# 2012_fdp_balise_mere.net
KiCad netlist of a schematic drawn in Altium Designer
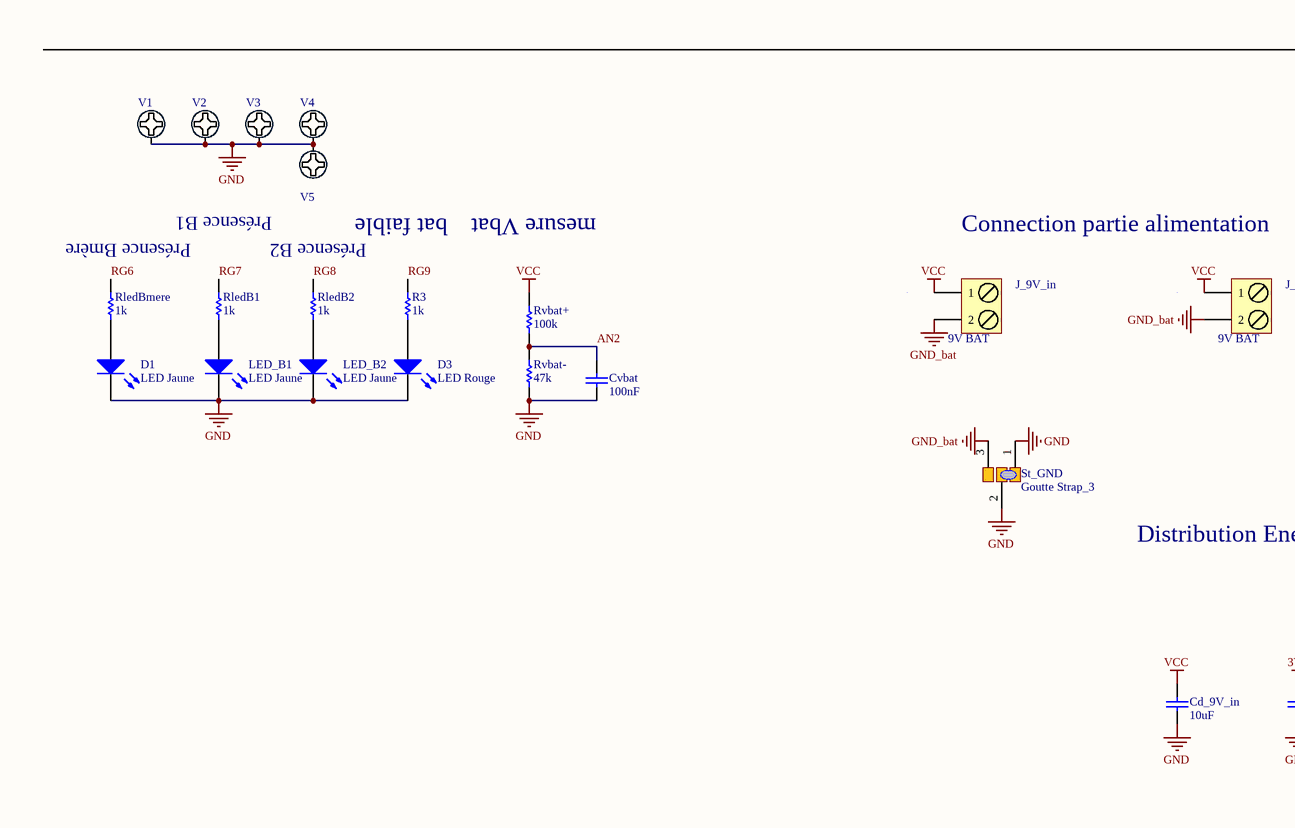
[diagram p0: 2012_fdp_balise_mere.SchDoc, left]
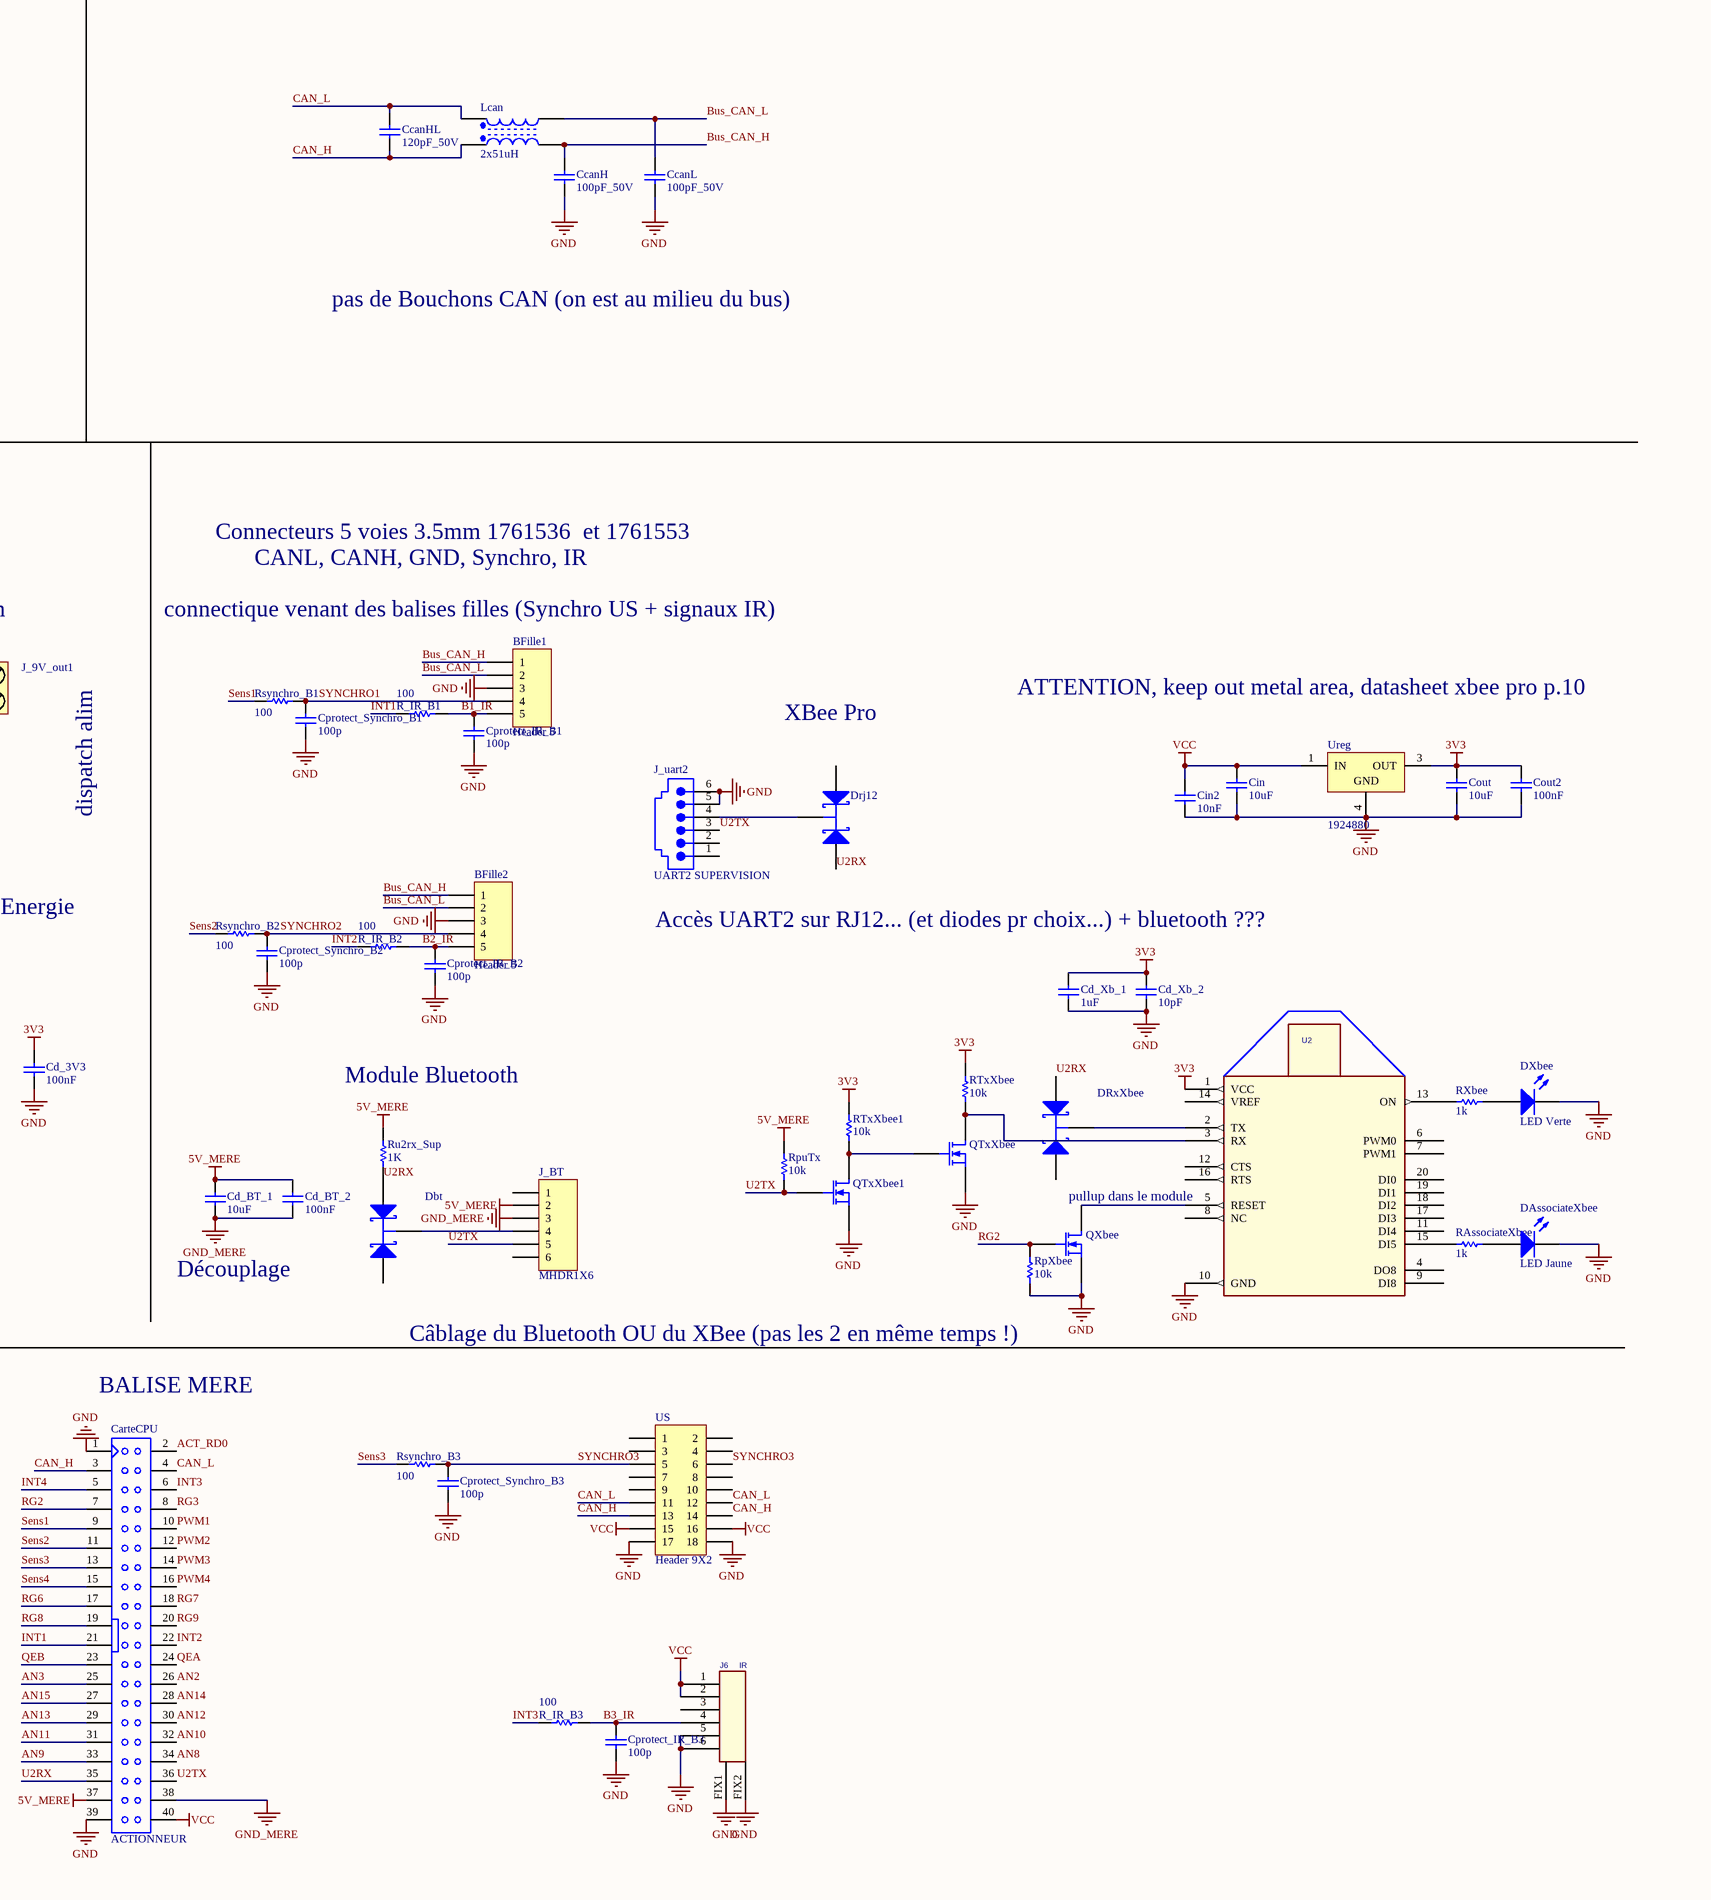
[diagram p1: 2012_fdp_balise_mere.SchDoc, right]

(export (version "E")
  (design (tool "Eeschema 10.0.6"))
  (components
    (comp (ref "BFille1")
      (value "Header 5")
      (footprint "BORNIER_5V_3.5MM")
      (description "Header, 5-Pin")
      (fields (field (name "PUBLISHER") "Altium Limited"))
      (libsource (lib "DG_Connecteur") (part "Header 5"))
    )
    (comp (ref "BFille2")
      (value "Header 5")
      (footprint "BORNIER_5V_3.5MM")
      (description "Header, 5-Pin")
      (fields (field (name "PUBLISHER") "Altium Limited"))
      (libsource (lib "DG_Connecteur") (part "Header 5"))
    )
    (comp (ref "CarteCPU")
      (value "ACTIONNEUR")
      (footprint "HE10/40_MAL_DROIT-FDP-ROBOT")
      (description "Connector; HE10; 40 Position; Male")
      (libsource (lib "miniprojet") (part "HE10/40"))
    )
    (comp (ref "CcanH")
      (value "100pF_50V")
      (footprint "C0603_N")
      (description "Capacitor")
      (fields (field (name "PUBLISHER") "Altium Limited"))
      (libsource (lib "DG_Condensateur") (part "Capacitor"))
    )
    (comp (ref "CcanHL")
      (value "120pF_50V")
      (footprint "C0603_N")
      (description "Capacitor")
      (fields (field (name "PUBLISHER") "Altium Limited"))
      (libsource (lib "DG_Condensateur") (part "Capacitor"))
    )
    (comp (ref "CcanL")
      (value "100pF_50V")
      (footprint "C0603_N")
      (description "Capacitor")
      (fields (field (name "PUBLISHER") "Altium Limited"))
      (libsource (lib "DG_Condensateur") (part "Capacitor"))
    )
    (comp (ref "Cd_3V3")
      (value "100nF")
      (footprint "C0805_N")
      (description "Capacitor")
      (fields (field (name "PUBLISHER") "Altium Limited"))
      (libsource (lib "_ROBOT") (part "Condensateur"))
    )
    (comp (ref "Cd_9V_in")
      (value "10uF")
      (footprint "C0805_N")
      (description "Capacitor")
      (fields (field (name "PUBLISHER") "Altium Limited"))
      (libsource (lib "_ROBOT") (part "Condensateur"))
    )
    (comp (ref "Cd_BT_1")
      (value "10uF")
      (footprint "C0805_N")
      (description "Capacitor")
      (fields (field (name "PUBLISHER") "Altium Limited"))
      (libsource (lib "_ROBOT") (part "Condensateur"))
    )
    (comp (ref "Cd_BT_2")
      (value "100nF")
      (footprint "C0805_N")
      (description "Capacitor")
      (fields (field (name "PUBLISHER") "Altium Limited"))
      (libsource (lib "_ROBOT") (part "Condensateur"))
    )
    (comp (ref "Cd_Xb_1")
      (value "1uF")
      (footprint "C0805_N")
      (description "Capacitor")
      (fields (field (name "PUBLISHER") "Altium Limited"))
      (libsource (lib "_ROBOT") (part "Condensateur"))
    )
    (comp (ref "Cd_Xb_2")
      (value "10pF")
      (footprint "C0805_N")
      (description "Capacitor")
      (fields (field (name "PUBLISHER") "Altium Limited"))
      (libsource (lib "_ROBOT") (part "Condensateur"))
    )
    (comp (ref "Cin")
      (value "10uF")
      (footprint "C1206_N")
      (description "Capacitor")
      (fields (field (name "PUBLISHER") "Altium Limited"))
      (libsource (lib "DG_Condensateur") (part "Capacitor"))
    )
    (comp (ref "Cin2")
      (value "10nF")
      (footprint "C0805_N")
      (description "Capacitor")
      (fields (field (name "PUBLISHER") "Altium Limited"))
      (libsource (lib "DG_Condensateur") (part "Capacitor"))
    )
    (comp (ref "Cout")
      (value "10uF")
      (footprint "C1206_N")
      (description "Capacitor")
      (fields (field (name "PUBLISHER") "Altium Limited"))
      (libsource (lib "DG_Condensateur") (part "Capacitor"))
    )
    (comp (ref "Cout2")
      (value "100nF")
      (footprint "C0805_N")
      (description "Capacitor")
      (fields (field (name "PUBLISHER") "Altium Limited"))
      (libsource (lib "DG_Condensateur") (part "Capacitor"))
    )
    (comp (ref "Cprotect_IR_B1")
      (value "100p")
      (footprint "C0805_N")
      (description "Capacitor")
      (fields (field (name "PUBLISHER") "Altium Limited"))
      (libsource (lib "DG_Condensateur") (part "Capacitor"))
    )
    (comp (ref "Cprotect_IR_B2")
      (value "100p")
      (footprint "C0805_N")
      (description "Capacitor")
      (fields (field (name "PUBLISHER") "Altium Limited"))
      (libsource (lib "DG_Condensateur") (part "Capacitor"))
    )
    (comp (ref "Cprotect_IR_B3")
      (value "100p")
      (footprint "C0805_N")
      (description "Capacitor")
      (fields (field (name "PUBLISHER") "Altium Limited"))
      (libsource (lib "DG_Condensateur") (part "Capacitor"))
    )
    (comp (ref "Cprotect_Synchro_B1")
      (value "100p")
      (footprint "C0805_N")
      (description "Capacitor")
      (fields (field (name "PUBLISHER") "Altium Limited"))
      (libsource (lib "DG_Condensateur") (part "Capacitor"))
    )
    (comp (ref "Cprotect_Synchro_B2")
      (value "100p")
      (footprint "C0805_N")
      (description "Capacitor")
      (fields (field (name "PUBLISHER") "Altium Limited"))
      (libsource (lib "DG_Condensateur") (part "Capacitor"))
    )
    (comp (ref "Cprotect_Synchro_B3")
      (value "100p")
      (footprint "C0805_N")
      (description "Capacitor")
      (fields (field (name "PUBLISHER") "Altium Limited"))
      (libsource (lib "DG_Condensateur") (part "Capacitor"))
    )
    (comp (ref "Cvbat")
      (value "100nF")
      (footprint "C0805_N")
      (description "Capacitor")
      (fields (field (name "PUBLISHER") "Altium Limited"))
      (libsource (lib "DG_Condensateur") (part "Capacitor"))
    )
    (comp (ref "D1")
      (value "LED Jaune")
      (footprint "LED_0805")
      (description "Typical LED")
      (fields (field (name "PUBLISHER") "Altium Limited"))
      (libsource (lib "_ROBOT") (part "LED"))
    )
    (comp (ref "D3")
      (value "LED Rouge")
      (footprint "LED_0805")
      (description "Typical LED")
      (fields (field (name "PUBLISHER") "Altium Limited"))
      (libsource (lib "_ROBOT") (part "LED"))
    )
    (comp (ref "DAssociateXbee")
      (value "LED Jaune")
      (footprint "LED_0805")
      (description "Typical LED")
      (fields (field (name "PUBLISHER") "Altium Limited"))
      (libsource (lib "_ROBOT") (part "LED"))
    )
    (comp (ref "Dbt")
      (value "Diode Shottky double BAT54C")
      (footprint "SOT23-3N")
      (description "DIODE SCHOTTKY DOUBLE")
      (fields (field (name "MANUFACTURER PART NUMBER") "BAT54C") (field (name "MANUFACTURER") "ZETEX"))
      (libsource (lib "_ROBOT") (part "Diode Shottky double BAT54C"))
    )
    (comp (ref "Drj12")
      (value "Diode Shottky double BAT54C")
      (footprint "SOT23-3N")
      (description "DIODE SCHOTTKY DOUBLE")
      (fields (field (name "MANUFACTURER PART NUMBER") "BAT54C") (field (name "MANUFACTURER") "ZETEX"))
      (libsource (lib "_ROBOT") (part "Diode Shottky double BAT54C"))
    )
    (comp (ref "DRxXbee")
      (value "Diode Shottky double BAT54C")
      (footprint "SOT23-3N")
      (description "DIODE SCHOTTKY DOUBLE")
      (fields (field (name "MANUFACTURER PART NUMBER") "BAT54C") (field (name "MANUFACTURER") "ZETEX"))
      (libsource (lib "_ROBOT") (part "Diode Shottky double BAT54C"))
    )
    (comp (ref "DXbee")
      (value "LED Verte")
      (footprint "LED_0805")
      (description "Typical LED")
      (fields (field (name "PUBLISHER") "Altium Limited"))
      (libsource (lib "_ROBOT") (part "LED"))
    )
    (comp (ref "J6")
      (value "IR")
      (footprint "RJ11_6/6 - droit")
      (libsource (lib "*") (part "CONNECTEUR_RJ12"))
    )
    (comp (ref "J_9V_in")
      (value "9V BAT")
      (footprint "BORNIER2")
      (description "Terminal blocks, 2 pins, pitch=5mm")
      (libsource (lib "miniprojet") (part "BORNIER2"))
    )
    (comp (ref "J_9V_out1")
      (value "9V BAT")
      (footprint "BORNIER2")
      (description "Terminal blocks, 2 pins, pitch=5mm")
      (libsource (lib "miniprojet") (part "BORNIER2"))
    )
    (comp (ref "J_BT")
      (value "MHDR1X6")
      (footprint "HE14_6")
      (description "Header, 6-Pin")
      (fields (field (name "PUBLISHER") "Altium Limited"))
      (libsource (lib "Miscellaneous Connectors") (part "MHDR1X6"))
    )
    (comp (ref "J_uart2")
      (value "UART2 SUPERVISION")
      (footprint "RJ11_6/6")
      (description "Right Angle, Standard Profile, Offset Latch DECconnect, Flangeless PCB Jack")
      (fields (field (name "PUBLISHER") "Altium Limited"))
      (libsource (lib "miniprojet") (part "RJ11_6/6"))
    )
    (comp (ref "Lcan")
      (value "2x51uH")
      (footprint "Self de mode commun Wurth Elektronik WE-SL2")
      (description "WUERTH ELEKTRONIK - WE-SL2 744 227 - FILTRE DE LIGNE MODE COMMUN CMS 2X51uH")
      (fields (field (name "MANUFACTURER") "WURTH ELEKTRONIK"))
      (libsource (lib "DG_Inductance") (part "Self de mode commun WE-744220"))
    )
    (comp (ref "LED_B1")
      (value "LED Jaune")
      (footprint "LED_0805")
      (description "Typical LED")
      (fields (field (name "PUBLISHER") "Altium Limited"))
      (libsource (lib "_ROBOT") (part "LED"))
    )
    (comp (ref "LED_B2")
      (value "LED Jaune")
      (footprint "LED_0805")
      (description "Typical LED")
      (fields (field (name "PUBLISHER") "Altium Limited"))
      (libsource (lib "_ROBOT") (part "LED"))
    )
    (comp (ref "QTxXbee")
      (value "Transistor MOSFET-N")
      (footprint "SOT23-3N")
      (description "N-Channel MOSFET")
      (fields (field (name "PUBLISHER") "Altium Limited"))
      (libsource (lib "_ROBOT") (part "Transistor MOSFET-N"))
    )
    (comp (ref "QTxXbee1")
      (value "Transistor MOSFET-N")
      (footprint "SOT23-3N")
      (description "N-Channel MOSFET")
      (fields (field (name "PUBLISHER") "Altium Limited"))
      (libsource (lib "_ROBOT") (part "Transistor MOSFET-N"))
    )
    (comp (ref "QXbee")
      (value "Transistor MOSFET-N")
      (footprint "SOT23-3N")
      (description "N-Channel MOSFET")
      (fields (field (name "PUBLISHER") "Altium Limited"))
      (libsource (lib "_ROBOT") (part "Transistor MOSFET-N"))
    )
    (comp (ref "R3")
      (value "1k")
      (footprint "R1206_N")
      (description "Resistor")
      (fields (field (name "PUBLISHER") "Altium Limited"))
      (libsource (lib "_ROBOT") (part "Resistor"))
    )
    (comp (ref "RAssociateXbee")
      (value "1k")
      (footprint "R1206_N")
      (description "Resistor")
      (fields (field (name "PUBLISHER") "Altium Limited"))
      (libsource (lib "_ROBOT") (part "Resistor"))
    )
    (comp (ref "RledB1")
      (value "1k")
      (footprint "R1206_N")
      (description "Resistor")
      (fields (field (name "PUBLISHER") "Altium Limited"))
      (libsource (lib "_ROBOT") (part "Resistor"))
    )
    (comp (ref "RledB2")
      (value "1k")
      (footprint "R1206_N")
      (description "Resistor")
      (fields (field (name "PUBLISHER") "Altium Limited"))
      (libsource (lib "_ROBOT") (part "Resistor"))
    )
    (comp (ref "RledBmere")
      (value "1k")
      (footprint "R1206_N")
      (description "Resistor")
      (fields (field (name "PUBLISHER") "Altium Limited"))
      (libsource (lib "_ROBOT") (part "Resistor"))
    )
    (comp (ref "RpuTx")
      (value "10k")
      (footprint "R1206_N")
      (description "Resistor")
      (fields (field (name "PUBLISHER") "Altium Limited"))
      (libsource (lib "_ROBOT") (part "Resistor"))
    )
    (comp (ref "RpXbee")
      (value "10k")
      (footprint "R1206_N")
      (description "Resistor")
      (fields (field (name "PUBLISHER") "Altium Limited"))
      (libsource (lib "_ROBOT") (part "Resistor"))
    )
    (comp (ref "Rsynchro_B1")
      (value "100")
      (footprint "R1206_N")
      (description "Resistor")
      (fields (field (name "PUBLISHER") "Altium Limited"))
      (libsource (lib "_ROBOT") (part "Resistor"))
    )
    (comp (ref "Rsynchro_B2")
      (value "100")
      (footprint "R1206_N")
      (description "Resistor")
      (fields (field (name "PUBLISHER") "Altium Limited"))
      (libsource (lib "_ROBOT") (part "Resistor"))
    )
    (comp (ref "Rsynchro_B3")
      (value "100")
      (footprint "R1206_N")
      (description "Resistor")
      (fields (field (name "PUBLISHER") "Altium Limited"))
      (libsource (lib "_ROBOT") (part "Resistor"))
    )
    (comp (ref "RTxXbee")
      (value "10k")
      (footprint "R1206_N")
      (description "Resistor")
      (fields (field (name "PUBLISHER") "Altium Limited"))
      (libsource (lib "_ROBOT") (part "Resistor"))
    )
    (comp (ref "RTxXbee1")
      (value "10k")
      (footprint "R1206_N")
      (description "Resistor")
      (fields (field (name "PUBLISHER") "Altium Limited"))
      (libsource (lib "_ROBOT") (part "Resistor"))
    )
    (comp (ref "Ru2rx_Sup")
      (value "1K")
      (footprint "R1206_N")
      (description "Resistor")
      (fields (field (name "PUBLISHER") "Altium Limited"))
      (libsource (lib "_ROBOT") (part "Resistor"))
    )
    (comp (ref "Rvbat+")
      (value "100k")
      (footprint "R1206_N")
      (description "Resistor")
      (fields (field (name "PUBLISHER") "Altium Limited"))
      (libsource (lib "_ROBOT") (part "Resistor"))
    )
    (comp (ref "Rvbat-")
      (value "47k")
      (footprint "R1206_N")
      (description "Resistor")
      (fields (field (name "PUBLISHER") "Altium Limited"))
      (libsource (lib "_ROBOT") (part "Resistor"))
    )
    (comp (ref "RXbee")
      (value "1k")
      (footprint "R1206_N")
      (description "Resistor")
      (fields (field (name "PUBLISHER") "Altium Limited"))
      (libsource (lib "_ROBOT") (part "Resistor"))
    )
    (comp (ref "R_IR_B1")
      (value "100")
      (footprint "R1206_N")
      (description "Resistor")
      (fields (field (name "PUBLISHER") "Altium Limited"))
      (libsource (lib "_ROBOT") (part "Resistor"))
    )
    (comp (ref "R_IR_B2")
      (value "100")
      (footprint "R1206_N")
      (description "Resistor")
      (fields (field (name "PUBLISHER") "Altium Limited"))
      (libsource (lib "_ROBOT") (part "Resistor"))
    )
    (comp (ref "R_IR_B3")
      (value "100")
      (footprint "R1206_N")
      (description "Resistor")
      (fields (field (name "PUBLISHER") "Altium Limited"))
      (libsource (lib "_ROBOT") (part "Resistor"))
    )
    (comp (ref "St_GND")
      (value "Goutte Strap_3")
      (footprint "Goutte Strap_3")
      (fields (field (name "PUBLISHER") "Damien Guitton"))
      (libsource (lib "DG_Connecteur") (part "Goutte Strap_3"))
    )
    (comp (ref "U2") (value "XBee") (footprint "MODULE_XBEE") (libsource (lib "*") (part "XBee")))
    (comp (ref "Ureg")
      (value "1924880")
      (footprint "369A-13")
      (description "Three-Terminal Positive Voltage Regulator")
      (fields (field (name "PUBLISHER") "Altium Limited"))
      (libsource (lib "ON Semi Power Mgt Voltage Regulator") (part "MC7805ACD2T"))
    )
    (comp (ref "US")
      (value "Header 9X2")
      (footprint "HDR2X9")
      (description "Header, 9-Pin, Dual row")
      (fields (field (name "PUBLISHER") "Altium Limited"))
      (libsource (lib "DG_Connecteur") (part "Header 9X2"))
    )
    (comp (ref "V1")
      (value "Pad_M3")
      (footprint "M3x6mm")
      (description "Vis M3 X 6mm _TORX_Tête 6mm")
      (fields (field (name "PUBLISHER") "Damien Guitton"))
      (libsource (lib "_ROBOT") (part "Vis M3 X 6mm _TORX_Tête 6mm"))
    )
    (comp (ref "V2")
      (value "Pad_M3")
      (footprint "M3x6mm")
      (description "Vis M3 X 6mm _TORX_Tête 6mm")
      (fields (field (name "PUBLISHER") "Damien Guitton"))
      (libsource (lib "_ROBOT") (part "Vis M3 X 6mm _TORX_Tête 6mm"))
    )
    (comp (ref "V3")
      (value "Pad_M3")
      (footprint "M3x6mm")
      (description "Vis M3 X 6mm _TORX_Tête 6mm")
      (fields (field (name "PUBLISHER") "Damien Guitton"))
      (libsource (lib "_ROBOT") (part "Vis M3 X 6mm _TORX_Tête 6mm"))
    )
    (comp (ref "V4")
      (value "Pad_M3")
      (footprint "M3x6mm")
      (description "Vis M3 X 6mm _TORX_Tête 6mm")
      (fields (field (name "PUBLISHER") "Damien Guitton"))
      (libsource (lib "_ROBOT") (part "Vis M3 X 6mm _TORX_Tête 6mm"))
    )
    (comp (ref "V5")
      (value "Pad_M3")
      (footprint "M3x6mm")
      (description "Vis M3 X 6mm _TORX_Tête 6mm")
      (fields (field (name "PUBLISHER") "Damien Guitton"))
      (libsource (lib "_ROBOT") (part "Vis M3 X 6mm _TORX_Tête 6mm"))
    )
  )
  (nets
    (net (code "1") (name "/ACT_RD0") (class "Default")
      (node (ref "CarteCPU") (pin "2") (pinfunction "2_2") (pintype "passive"))
    )
    (net (code "2") (name "/AN2") (class "Default")
      (node (ref "CarteCPU") (pin "26") (pinfunction "26_26") (pintype "passive"))
      (node (ref "Cvbat") (pin "1") (pinfunction "1_1") (pintype "passive"))
      (node (ref "Rvbat+") (pin "2") (pinfunction "2_2") (pintype "passive"))
      (node (ref "Rvbat-") (pin "1") (pinfunction "1_1") (pintype "passive"))
    )
    (net (code "3") (name "/AN3") (class "Default")
      (node (ref "CarteCPU") (pin "25") (pinfunction "25_25") (pintype "passive"))
    )
    (net (code "4") (name "/AN8") (class "Default")
      (node (ref "CarteCPU") (pin "34") (pinfunction "34_34") (pintype "passive"))
    )
    (net (code "5") (name "/AN9") (class "Default")
      (node (ref "CarteCPU") (pin "33") (pinfunction "33_33") (pintype "passive"))
    )
    (net (code "6") (name "/AN10") (class "Default")
      (node (ref "CarteCPU") (pin "32") (pinfunction "32_32") (pintype "passive"))
    )
    (net (code "7") (name "/AN11") (class "Default")
      (node (ref "CarteCPU") (pin "31") (pinfunction "31_31") (pintype "passive"))
    )
    (net (code "8") (name "/AN12") (class "Default")
      (node (ref "CarteCPU") (pin "30") (pinfunction "30_30") (pintype "passive"))
    )
    (net (code "9") (name "/AN13") (class "Default")
      (node (ref "CarteCPU") (pin "29") (pinfunction "29_29") (pintype "passive"))
    )
    (net (code "10") (name "/AN14") (class "Default")
      (node (ref "CarteCPU") (pin "28") (pinfunction "28_28") (pintype "passive"))
    )
    (net (code "11") (name "/AN15") (class "Default")
      (node (ref "CarteCPU") (pin "27") (pinfunction "27_27") (pintype "passive"))
    )
    (net (code "12") (name "/B1_IR") (class "Default")
      (node (ref "BFille1") (pin "5") (pinfunction "5_5") (pintype "passive"))
      (node (ref "Cprotect_IR_B1") (pin "1") (pinfunction "1_1") (pintype "passive"))
      (node (ref "R_IR_B1") (pin "2") (pinfunction "2_2") (pintype "passive"))
    )
    (net (code "13") (name "/B2_IR") (class "Default")
      (node (ref "BFille2") (pin "5") (pinfunction "5_5") (pintype "passive"))
      (node (ref "Cprotect_IR_B2") (pin "1") (pinfunction "1_1") (pintype "passive"))
      (node (ref "R_IR_B2") (pin "2") (pinfunction "2_2") (pintype "passive"))
    )
    (net (code "14") (name "/B3_IR") (class "Default")
      (node (ref "Cprotect_IR_B3") (pin "1") (pinfunction "1_1") (pintype "passive"))
      (node (ref "J6") (pin "4") (pinfunction "4_4") (pintype "passive"))
      (node (ref "R_IR_B3") (pin "2") (pinfunction "2_2") (pintype "passive"))
    )
    (net (code "15") (name "/Bus_CAN_H") (class "Default")
      (node (ref "BFille1") (pin "1") (pinfunction "1_1") (pintype "passive"))
      (node (ref "BFille2") (pin "1") (pinfunction "1_1") (pintype "passive"))
      (node (ref "CcanH") (pin "2") (pinfunction "2_2") (pintype "passive"))
      (node (ref "Lcan") (pin "4") (pinfunction "4_4") (pintype "passive"))
    )
    (net (code "16") (name "/Bus_CAN_L") (class "Default")
      (node (ref "BFille1") (pin "2") (pinfunction "2_2") (pintype "passive"))
      (node (ref "BFille2") (pin "2") (pinfunction "2_2") (pintype "passive"))
      (node (ref "CcanL") (pin "2") (pinfunction "2_2") (pintype "passive"))
      (node (ref "Lcan") (pin "3") (pinfunction "3_3") (pintype "passive"))
    )
    (net (code "17") (name "/CAN_H") (class "Default")
      (node (ref "CarteCPU") (pin "3") (pinfunction "3_3") (pintype "passive"))
      (node (ref "CcanHL") (pin "1") (pinfunction "1_1") (pintype "passive"))
      (node (ref "Lcan") (pin "1") (pinfunction "1_1") (pintype "passive"))
      (node (ref "US") (pin "13") (pinfunction "13_13") (pintype "passive"))
      (node (ref "US") (pin "14") (pinfunction "14_14") (pintype "passive"))
    )
    (net (code "18") (name "/CAN_L") (class "Default")
      (node (ref "CarteCPU") (pin "4") (pinfunction "4_4") (pintype "passive"))
      (node (ref "CcanHL") (pin "2") (pinfunction "2_2") (pintype "passive"))
      (node (ref "Lcan") (pin "2") (pinfunction "2_2") (pintype "passive"))
      (node (ref "US") (pin "11") (pinfunction "11_11") (pintype "passive"))
      (node (ref "US") (pin "12") (pinfunction "12_12") (pintype "passive"))
    )
    (net (code "19") (name "/INT1") (class "Default")
      (node (ref "CarteCPU") (pin "21") (pinfunction "21_21") (pintype "passive"))
      (node (ref "R_IR_B1") (pin "1") (pinfunction "1_1") (pintype "passive"))
    )
    (net (code "20") (name "/INT2") (class "Default")
      (node (ref "CarteCPU") (pin "22") (pinfunction "22_22") (pintype "passive"))
      (node (ref "R_IR_B2") (pin "1") (pinfunction "1_1") (pintype "passive"))
    )
    (net (code "21") (name "/INT3") (class "Default")
      (node (ref "CarteCPU") (pin "6") (pinfunction "6_6") (pintype "passive"))
      (node (ref "R_IR_B3") (pin "1") (pinfunction "1_1") (pintype "passive"))
    )
    (net (code "22") (name "/INT4") (class "Default")
      (node (ref "CarteCPU") (pin "5") (pinfunction "5_5") (pintype "passive"))
    )
    (net (code "23") (name "/PWM1") (class "Default")
      (node (ref "CarteCPU") (pin "10") (pinfunction "10_10") (pintype "passive"))
    )
    (net (code "24") (name "/PWM2") (class "Default")
      (node (ref "CarteCPU") (pin "12") (pinfunction "12_12") (pintype "passive"))
    )
    (net (code "25") (name "/PWM3") (class "Default")
      (node (ref "CarteCPU") (pin "14") (pinfunction "14_14") (pintype "passive"))
    )
    (net (code "26") (name "/PWM4") (class "Default")
      (node (ref "CarteCPU") (pin "16") (pinfunction "16_16") (pintype "passive"))
    )
    (net (code "27") (name "/QEA") (class "Default")
      (node (ref "CarteCPU") (pin "24") (pinfunction "24_24") (pintype "passive"))
    )
    (net (code "28") (name "/QEB") (class "Default")
      (node (ref "CarteCPU") (pin "23") (pinfunction "23_23") (pintype "passive"))
    )
    (net (code "29") (name "/RG2") (class "Default")
      (node (ref "CarteCPU") (pin "7") (pinfunction "7_7") (pintype "passive"))
      (node (ref "QXbee") (pin "2") (pinfunction "G_2") (pintype "passive"))
      (node (ref "RpXbee") (pin "1") (pinfunction "1_1") (pintype "passive"))
    )
    (net (code "30") (name "/RG3") (class "Default")
      (node (ref "CarteCPU") (pin "8") (pinfunction "8_8") (pintype "passive"))
    )
    (net (code "31") (name "/RG6") (class "Default")
      (node (ref "CarteCPU") (pin "17") (pinfunction "17_17") (pintype "passive"))
      (node (ref "RledBmere") (pin "1") (pinfunction "1_1") (pintype "passive"))
    )
    (net (code "32") (name "/RG7") (class "Default")
      (node (ref "CarteCPU") (pin "18") (pinfunction "18_18") (pintype "passive"))
      (node (ref "RledB1") (pin "2") (pinfunction "2_2") (pintype "passive"))
    )
    (net (code "33") (name "/RG8") (class "Default")
      (node (ref "CarteCPU") (pin "19") (pinfunction "19_19") (pintype "passive"))
      (node (ref "RledB2") (pin "2") (pinfunction "2_2") (pintype "passive"))
    )
    (net (code "34") (name "/RG9") (class "Default")
      (node (ref "CarteCPU") (pin "20") (pinfunction "20_20") (pintype "passive"))
      (node (ref "R3") (pin "1") (pinfunction "1_1") (pintype "passive"))
    )
    (net (code "35") (name "/SYNCHRO1") (class "Default")
      (node (ref "BFille1") (pin "4") (pinfunction "4_4") (pintype "passive"))
      (node (ref "Cprotect_Synchro_B1") (pin "1") (pinfunction "1_1") (pintype "passive"))
      (node (ref "Rsynchro_B1") (pin "2") (pinfunction "2_2") (pintype "passive"))
    )
    (net (code "36") (name "/SYNCHRO2") (class "Default")
      (node (ref "BFille2") (pin "4") (pinfunction "4_4") (pintype "passive"))
      (node (ref "Cprotect_Synchro_B2") (pin "1") (pinfunction "1_1") (pintype "passive"))
      (node (ref "Rsynchro_B2") (pin "2") (pinfunction "2_2") (pintype "passive"))
    )
    (net (code "37") (name "/SYNCHRO3") (class "Default")
      (node (ref "Cprotect_Synchro_B3") (pin "1") (pinfunction "1_1") (pintype "passive"))
      (node (ref "Rsynchro_B3") (pin "2") (pinfunction "2_2") (pintype "passive"))
      (node (ref "US") (pin "5") (pinfunction "5_5") (pintype "passive"))
      (node (ref "US") (pin "6") (pinfunction "6_6") (pintype "passive"))
    )
    (net (code "38") (name "/Sens1") (class "Default")
      (node (ref "CarteCPU") (pin "9") (pinfunction "9_9") (pintype "passive"))
      (node (ref "Rsynchro_B1") (pin "1") (pinfunction "1_1") (pintype "passive"))
    )
    (net (code "39") (name "/Sens2") (class "Default")
      (node (ref "CarteCPU") (pin "11") (pinfunction "11_11") (pintype "passive"))
      (node (ref "Rsynchro_B2") (pin "1") (pinfunction "1_1") (pintype "passive"))
    )
    (net (code "40") (name "/Sens3") (class "Default")
      (node (ref "CarteCPU") (pin "13") (pinfunction "13_13") (pintype "passive"))
      (node (ref "Rsynchro_B3") (pin "1") (pinfunction "1_1") (pintype "passive"))
    )
    (net (code "41") (name "/Sens4") (class "Default")
      (node (ref "CarteCPU") (pin "15") (pinfunction "15_15") (pintype "passive"))
    )
    (net (code "42") (name "/U2RX") (class "Default")
      (node (ref "CarteCPU") (pin "35") (pinfunction "35_35") (pintype "passive"))
      (node (ref "DRxXbee") (pin "1") (pinfunction "A1_1") (pintype "passive"))
      (node (ref "Dbt") (pin "1") (pinfunction "A1_1") (pintype "passive"))
      (node (ref "Drj12") (pin "1") (pinfunction "A1_1") (pintype "passive"))
      (node (ref "Ru2rx_Sup") (pin "1") (pinfunction "1_1") (pintype "passive"))
    )
    (net (code "43") (name "/U2TX") (class "Default")
      (node (ref "CarteCPU") (pin "36") (pinfunction "36_36") (pintype "passive"))
      (node (ref "J_BT") (pin "5") (pinfunction "5_5") (pintype "passive"))
      (node (ref "J_uart2") (pin "3") (pinfunction "3_3") (pintype "passive"))
      (node (ref "QTxXbee1") (pin "2") (pinfunction "G_2") (pintype "passive"))
      (node (ref "RpuTx") (pin "2") (pinfunction "2_2") (pintype "passive"))
    )
    (net (code "44") (name "3V3") (class "Default")
      (node (ref "Cd_3V3") (pin "2") (pinfunction "2_2") (pintype "passive"))
      (node (ref "Cd_Xb_1") (pin "2") (pinfunction "2_2") (pintype "passive"))
      (node (ref "Cd_Xb_2") (pin "2") (pinfunction "2_2") (pintype "passive"))
      (node (ref "Cout") (pin "2") (pinfunction "2_2") (pintype "passive"))
      (node (ref "Cout2") (pin "2") (pinfunction "2_2") (pintype "passive"))
      (node (ref "RTxXbee") (pin "1") (pinfunction "1_1") (pintype "passive"))
      (node (ref "RTxXbee1") (pin "1") (pinfunction "1_1") (pintype "passive"))
      (node (ref "U2") (pin "1") (pinfunction "VCC_1") (pintype "output"))
      (node (ref "Ureg") (pin "3") (pinfunction "OUT_3") (pintype "power_in"))
    )
    (net (code "45") (name "5V_MERE") (class "Default")
      (node (ref "CarteCPU") (pin "37") (pinfunction "37_37") (pintype "passive"))
      (node (ref "Cd_BT_1") (pin "2") (pinfunction "2_2") (pintype "passive"))
      (node (ref "Cd_BT_2") (pin "2") (pinfunction "2_2") (pintype "passive"))
      (node (ref "J_BT") (pin "2") (pinfunction "2_2") (pintype "passive"))
      (node (ref "RpuTx") (pin "1") (pinfunction "1_1") (pintype "passive"))
      (node (ref "Ru2rx_Sup") (pin "2") (pinfunction "2_2") (pintype "passive"))
    )
    (net (code "46") (name "GND") (class "Default")
      (node (ref "BFille1") (pin "3") (pinfunction "3_3") (pintype "passive"))
      (node (ref "BFille2") (pin "3") (pinfunction "3_3") (pintype "passive"))
      (node (ref "CarteCPU") (pin "1") (pinfunction "1_1") (pintype "passive"))
      (node (ref "CarteCPU") (pin "39") (pinfunction "39_39") (pintype "passive"))
      (node (ref "CcanH") (pin "1") (pinfunction "1_1") (pintype "passive"))
      (node (ref "CcanL") (pin "1") (pinfunction "1_1") (pintype "passive"))
      (node (ref "Cd_3V3") (pin "1") (pinfunction "1_1") (pintype "passive"))
      (node (ref "Cd_9V_in") (pin "1") (pinfunction "1_1") (pintype "passive"))
      (node (ref "Cd_Xb_1") (pin "1") (pinfunction "1_1") (pintype "passive"))
      (node (ref "Cd_Xb_2") (pin "1") (pinfunction "1_1") (pintype "passive"))
      (node (ref "Cin") (pin "1") (pinfunction "1_1") (pintype "passive"))
      (node (ref "Cin2") (pin "1") (pinfunction "1_1") (pintype "passive"))
      (node (ref "Cout") (pin "1") (pinfunction "1_1") (pintype "passive"))
      (node (ref "Cout2") (pin "1") (pinfunction "1_1") (pintype "passive"))
      (node (ref "Cprotect_IR_B1") (pin "2") (pinfunction "2_2") (pintype "passive"))
      (node (ref "Cprotect_IR_B2") (pin "2") (pinfunction "2_2") (pintype "passive"))
      (node (ref "Cprotect_IR_B3") (pin "2") (pinfunction "2_2") (pintype "passive"))
      (node (ref "Cprotect_Synchro_B1") (pin "2") (pinfunction "2_2") (pintype "passive"))
      (node (ref "Cprotect_Synchro_B2") (pin "2") (pinfunction "2_2") (pintype "passive"))
      (node (ref "Cprotect_Synchro_B3") (pin "2") (pinfunction "2_2") (pintype "passive"))
      (node (ref "Cvbat") (pin "2") (pinfunction "2_2") (pintype "passive"))
      (node (ref "D1") (pin "2") (pinfunction "K_2") (pintype "passive"))
      (node (ref "D3") (pin "2") (pinfunction "K_2") (pintype "passive"))
      (node (ref "DAssociateXbee") (pin "2") (pinfunction "K_2") (pintype "passive"))
      (node (ref "DXbee") (pin "2") (pinfunction "K_2") (pintype "passive"))
      (node (ref "J6") (pin "5") (pinfunction "5_5") (pintype "passive"))
      (node (ref "J6") (pin "6") (pinfunction "6_6") (pintype "passive"))
      (node (ref "J6") (pin "FIX1") (pinfunction "FIX1_FIX1") (pintype "passive"))
      (node (ref "J6") (pin "FIX2") (pinfunction "FIX2_FIX2") (pintype "passive"))
      (node (ref "J_uart2") (pin "5") (pinfunction "5_5") (pintype "passive"))
      (node (ref "J_uart2") (pin "6") (pinfunction "6_6") (pintype "passive"))
      (node (ref "LED_B1") (pin "2") (pinfunction "K_2") (pintype "passive"))
      (node (ref "LED_B2") (pin "2") (pinfunction "K_2") (pintype "passive"))
      (node (ref "QTxXbee") (pin "3") (pinfunction "S_3") (pintype "passive"))
      (node (ref "QTxXbee1") (pin "3") (pinfunction "S_3") (pintype "passive"))
      (node (ref "QXbee") (pin "3") (pinfunction "S_3") (pintype "passive"))
      (node (ref "RpXbee") (pin "2") (pinfunction "2_2") (pintype "passive"))
      (node (ref "Rvbat-") (pin "2") (pinfunction "2_2") (pintype "passive"))
      (node (ref "St_GND") (pin "1") (pinfunction "1_1") (pintype "passive"))
      (node (ref "St_GND") (pin "2") (pinfunction "2_2") (pintype "passive"))
      (node (ref "U2") (pin "10") (pinfunction "GND_10") (pintype "output"))
      (node (ref "US") (pin "17") (pinfunction "17_17") (pintype "passive"))
      (node (ref "US") (pin "18") (pinfunction "18_18") (pintype "passive"))
      (node (ref "Ureg") (pin "4") (pinfunction "GND_4") (pintype "power_in"))
      (node (ref "V1") (pin "1") (pinfunction "1_1") (pintype "passive"))
      (node (ref "V2") (pin "1") (pinfunction "1_1") (pintype "passive"))
      (node (ref "V3") (pin "1") (pinfunction "1_1") (pintype "passive"))
      (node (ref "V4") (pin "1") (pinfunction "1_1") (pintype "passive"))
      (node (ref "V5") (pin "1") (pinfunction "1_1") (pintype "passive"))
    )
    (net (code "47") (name "GND_MERE") (class "Default")
      (node (ref "CarteCPU") (pin "38") (pinfunction "38_38") (pintype "passive"))
      (node (ref "Cd_BT_1") (pin "1") (pinfunction "1_1") (pintype "passive"))
      (node (ref "Cd_BT_2") (pin "1") (pinfunction "1_1") (pintype "passive"))
      (node (ref "J_BT") (pin "3") (pinfunction "3_3") (pintype "passive"))
    )
    (net (code "48") (name "GND_bat") (class "Default")
      (node (ref "J_9V_in") (pin "2") (pinfunction "2_2") (pintype "passive"))
      (node (ref "J_9V_out1") (pin "2") (pinfunction "2_2") (pintype "passive"))
      (node (ref "St_GND") (pin "3") (pinfunction "3_3") (pintype "passive"))
    )
    (net (code "49") (name "Net-(D1-A)") (class "Default")
      (node (ref "D1") (pin "1") (pinfunction "A_1") (pintype "passive"))
      (node (ref "RledBmere") (pin "2") (pinfunction "2_2") (pintype "passive"))
    )
    (net (code "50") (name "Net-(D3-A)") (class "Default")
      (node (ref "D3") (pin "1") (pinfunction "A_1") (pintype "passive"))
      (node (ref "R3") (pin "2") (pinfunction "2_2") (pintype "passive"))
    )
    (net (code "51") (name "Net-(DAssociateXbee-A)") (class "Default")
      (node (ref "DAssociateXbee") (pin "1") (pinfunction "A_1") (pintype "passive"))
      (node (ref "RAssociateXbee") (pin "2") (pinfunction "2_2") (pintype "passive"))
    )
    (net (code "52") (name "Net-(DRxXbee-K)") (class "Default")
      (node (ref "DRxXbee") (pin "3") (pinfunction "K_3") (pintype "passive"))
      (node (ref "U2") (pin "2") (pinfunction "TX_2") (pintype "output"))
    )
    (net (code "53") (name "Net-(DXbee-A)") (class "Default")
      (node (ref "DXbee") (pin "1") (pinfunction "A_1") (pintype "passive"))
      (node (ref "RXbee") (pin "2") (pinfunction "2_2") (pintype "passive"))
    )
    (net (code "54") (name "Net-(Dbt-K)") (class "Default")
      (node (ref "Dbt") (pin "3") (pinfunction "K_3") (pintype "passive"))
      (node (ref "J_BT") (pin "4") (pinfunction "4_4") (pintype "passive"))
    )
    (net (code "55") (name "Net-(Drj12-K)") (class "Default")
      (node (ref "Drj12") (pin "3") (pinfunction "K_3") (pintype "passive"))
      (node (ref "J_uart2") (pin "4") (pinfunction "4_4") (pintype "passive"))
    )
    (net (code "56") (name "Net-(LED_B1-A)") (class "Default")
      (node (ref "LED_B1") (pin "1") (pinfunction "A_1") (pintype "passive"))
      (node (ref "RledB1") (pin "1") (pinfunction "1_1") (pintype "passive"))
    )
    (net (code "57") (name "Net-(LED_B2-A)") (class "Default")
      (node (ref "LED_B2") (pin "1") (pinfunction "A_1") (pintype "passive"))
      (node (ref "RledB2") (pin "1") (pinfunction "1_1") (pintype "passive"))
    )
    (net (code "58") (name "Net-(QTxXbee-D)") (class "Default")
      (node (ref "QTxXbee") (pin "1") (pinfunction "D_1") (pintype "passive"))
      (node (ref "RTxXbee") (pin "2") (pinfunction "2_2") (pintype "passive"))
      (node (ref "U2") (pin "3") (pinfunction "RX_3") (pintype "output"))
    )
    (net (code "59") (name "Net-(QTxXbee-G)") (class "Default")
      (node (ref "QTxXbee") (pin "2") (pinfunction "G_2") (pintype "passive"))
      (node (ref "QTxXbee1") (pin "1") (pinfunction "D_1") (pintype "passive"))
      (node (ref "RTxXbee1") (pin "2") (pinfunction "2_2") (pintype "passive"))
    )
    (net (code "60") (name "Net-(QXbee-D)") (class "Default")
      (node (ref "QXbee") (pin "1") (pinfunction "D_1") (pintype "passive"))
      (node (ref "U2") (pin "5") (pinfunction "RESET_5") (pintype "output"))
    )
    (net (code "61") (name "Net-(U2-DI5)") (class "Default")
      (node (ref "RAssociateXbee") (pin "1") (pinfunction "1_1") (pintype "passive"))
      (node (ref "U2") (pin "15") (pinfunction "DI5_15") (pintype "passive"))
    )
    (net (code "62") (name "Net-(U2-ON)") (class "Default")
      (node (ref "RXbee") (pin "1") (pinfunction "1_1") (pintype "passive"))
      (node (ref "U2") (pin "13") (pinfunction "ON_13") (pintype "output"))
    )
    (net (code "63") (name "VCC") (class "Default")
      (node (ref "CarteCPU") (pin "40") (pinfunction "40_40") (pintype "passive"))
      (node (ref "Cd_9V_in") (pin "2") (pinfunction "2_2") (pintype "passive"))
      (node (ref "Cin") (pin "2") (pinfunction "2_2") (pintype "passive"))
      (node (ref "Cin2") (pin "2") (pinfunction "2_2") (pintype "passive"))
      (node (ref "J6") (pin "1") (pinfunction "1_1") (pintype "passive"))
      (node (ref "J6") (pin "2") (pinfunction "2_2") (pintype "passive"))
      (node (ref "J_9V_in") (pin "1") (pinfunction "1_1") (pintype "passive"))
      (node (ref "J_9V_out1") (pin "1") (pinfunction "1_1") (pintype "passive"))
      (node (ref "Rvbat+") (pin "1") (pinfunction "1_1") (pintype "passive"))
      (node (ref "US") (pin "15") (pinfunction "15_15") (pintype "passive"))
      (node (ref "US") (pin "16") (pinfunction "16_16") (pintype "passive"))
      (node (ref "Ureg") (pin "1") (pinfunction "IN_1") (pintype "power_in"))
    )
    (net (code "64") (name "unconnected-(DRxXbee-A2-Pad2)") (class "Default")
      (node (ref "DRxXbee") (pin "2") (pinfunction "A2_2") (pintype "passive"))
    )
    (net (code "65") (name "unconnected-(Dbt-A2-Pad2)") (class "Default")
      (node (ref "Dbt") (pin "2") (pinfunction "A2_2") (pintype "passive"))
    )
    (net (code "66") (name "unconnected-(Drj12-A2-Pad2)") (class "Default")
      (node (ref "Drj12") (pin "2") (pinfunction "A2_2") (pintype "passive"))
    )
    (net (code "67") (name "unconnected-(J6-Pad3)") (class "Default")
      (node (ref "J6") (pin "3") (pinfunction "3_3") (pintype "passive"))
    )
    (net (code "68") (name "unconnected-(J_BT-Pad1)") (class "Default")
      (node (ref "J_BT") (pin "1") (pinfunction "1_1") (pintype "passive"))
    )
    (net (code "69") (name "unconnected-(J_BT-Pad6)") (class "Default")
      (node (ref "J_BT") (pin "6") (pinfunction "6_6") (pintype "passive"))
    )
    (net (code "70") (name "unconnected-(J_uart2-Pad1)") (class "Default")
      (node (ref "J_uart2") (pin "1") (pinfunction "1_1") (pintype "passive"))
    )
    (net (code "71") (name "unconnected-(J_uart2-Pad2)") (class "Default")
      (node (ref "J_uart2") (pin "2") (pinfunction "2_2") (pintype "passive"))
    )
    (net (code "72") (name "unconnected-(U2-CTS-Pad12)") (class "Default")
      (node (ref "U2") (pin "12") (pinfunction "CTS_12") (pintype "output"))
    )
    (net (code "73") (name "unconnected-(U2-DI0-Pad20)") (class "Default")
      (node (ref "U2") (pin "20") (pinfunction "DI0_20") (pintype "passive"))
    )
    (net (code "74") (name "unconnected-(U2-DI1-Pad19)") (class "Default")
      (node (ref "U2") (pin "19") (pinfunction "DI1_19") (pintype "passive"))
    )
    (net (code "75") (name "unconnected-(U2-DI2-Pad18)") (class "Default")
      (node (ref "U2") (pin "18") (pinfunction "DI2_18") (pintype "passive"))
    )
    (net (code "76") (name "unconnected-(U2-DI3-Pad17)") (class "Default")
      (node (ref "U2") (pin "17") (pinfunction "DI3_17") (pintype "passive"))
    )
    (net (code "77") (name "unconnected-(U2-DI4-Pad11)") (class "Default")
      (node (ref "U2") (pin "11") (pinfunction "DI4_11") (pintype "passive"))
    )
    (net (code "78") (name "unconnected-(U2-DI8-Pad9)") (class "Default")
      (node (ref "U2") (pin "9") (pinfunction "DI8_9") (pintype "passive"))
    )
    (net (code "79") (name "unconnected-(U2-DO8-Pad4)") (class "Default")
      (node (ref "U2") (pin "4") (pinfunction "DO8_4") (pintype "passive"))
    )
    (net (code "80") (name "unconnected-(U2-NC-Pad8)") (class "Default")
      (node (ref "U2") (pin "8") (pinfunction "NC_8") (pintype "output"))
    )
    (net (code "81") (name "unconnected-(U2-PWM0-Pad6)") (class "Default")
      (node (ref "U2") (pin "6") (pinfunction "PWM0_6") (pintype "passive"))
    )
    (net (code "82") (name "unconnected-(U2-PWM1-Pad7)") (class "Default")
      (node (ref "U2") (pin "7") (pinfunction "PWM1_7") (pintype "passive"))
    )
    (net (code "83") (name "unconnected-(U2-RTS-Pad16)") (class "Default")
      (node (ref "U2") (pin "16") (pinfunction "RTS_16") (pintype "output"))
    )
    (net (code "84") (name "unconnected-(U2-VREF-Pad14)") (class "Default")
      (node (ref "U2") (pin "14") (pinfunction "VREF_14") (pintype "output"))
    )
    (net (code "85") (name "unconnected-(US-Pad1)") (class "Default")
      (node (ref "US") (pin "1") (pinfunction "1_1") (pintype "passive"))
    )
    (net (code "86") (name "unconnected-(US-Pad2)") (class "Default")
      (node (ref "US") (pin "2") (pinfunction "2_2") (pintype "passive"))
    )
    (net (code "87") (name "unconnected-(US-Pad3)") (class "Default")
      (node (ref "US") (pin "3") (pinfunction "3_3") (pintype "passive"))
    )
    (net (code "88") (name "unconnected-(US-Pad4)") (class "Default")
      (node (ref "US") (pin "4") (pinfunction "4_4") (pintype "passive"))
    )
    (net (code "89") (name "unconnected-(US-Pad7)") (class "Default")
      (node (ref "US") (pin "7") (pinfunction "7_7") (pintype "passive"))
    )
    (net (code "90") (name "unconnected-(US-Pad8)") (class "Default")
      (node (ref "US") (pin "8") (pinfunction "8_8") (pintype "passive"))
    )
    (net (code "91") (name "unconnected-(US-Pad9)") (class "Default")
      (node (ref "US") (pin "9") (pinfunction "9_9") (pintype "passive"))
    )
    (net (code "92") (name "unconnected-(US-Pad10)") (class "Default")
      (node (ref "US") (pin "10") (pinfunction "10_10") (pintype "passive"))
    )
  )
)
